# Audio.net
KiCad netlist of a schematic drawn in Altium Designer
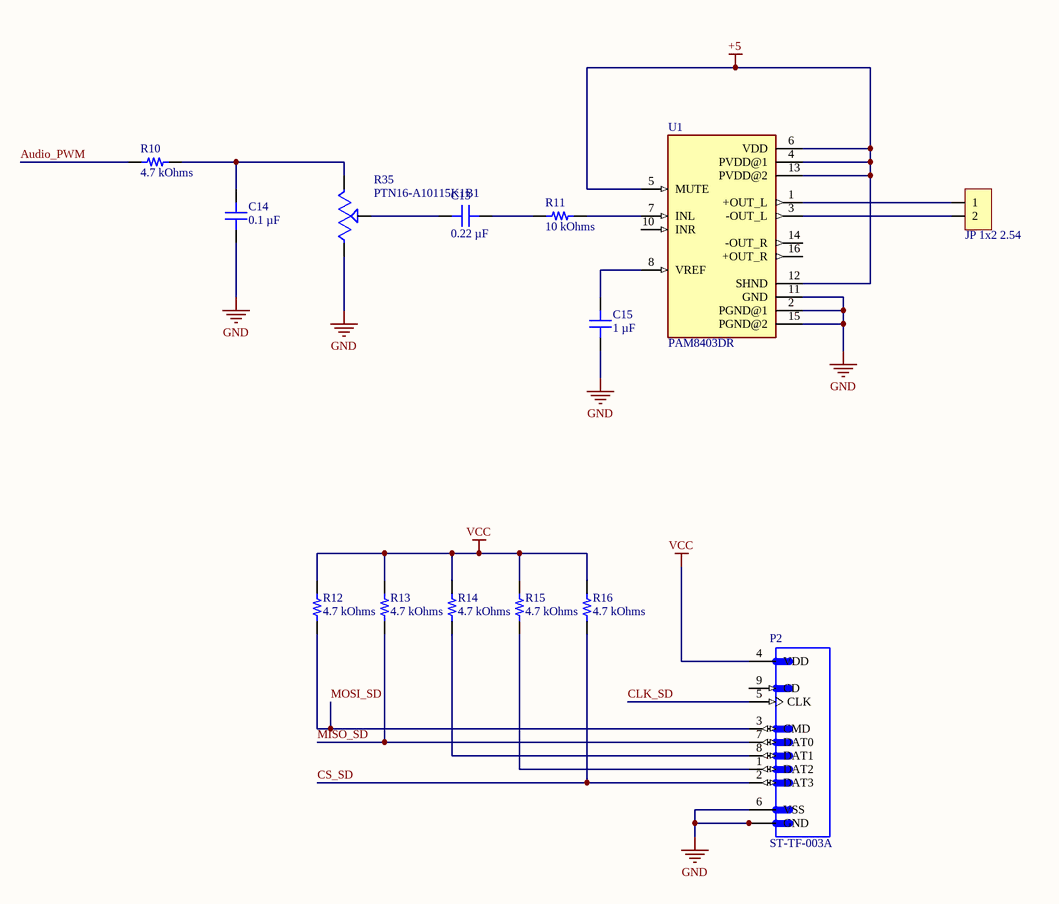
[diagram p0: Audio.SchDoc]

(export (version "E")
  (design (tool "Eeschema 10.0.6"))
  (components
    (comp (ref "C13")
      (value "0.22 µF")
      (footprint "CAP 0603_1608")
      (description "CAP CER 0.22UF 10V X7R 0603")
      (fields (field (name "PART NUMBER") "KGM15BR71A224MT") (field (name "MANUFACTURER") "KYOCERA AVX"))
      (libsource (lib "Celestial Altium Library - altium_library") (part "Capacitor"))
    )
    (comp (ref "C14")
      (value "0.1 µF")
      (footprint "CAP 0603_1608")
      (description "CAP CER 0.1UF 10V X7R 0603")
      (fields
        (field (name "PART NUMBER") "CX0603MRX7R6BB104")
        (field (name "MANUFACTURER") "PulseLarsen Antennas")
      )
      (libsource (lib "Celestial Altium Library - altium_library") (part "Capacitor"))
    )
    (comp (ref "C15")
      (value "1 µF")
      (footprint "CAP 0603_1608")
      (description "CAP CER 1UF 10V X7R 0603")
      (fields (field (name "PART NUMBER") "CM105X7R105M10AT") (field (name "MANUFACTURER") "KYOCERA AVX"))
      (libsource (lib "Celestial Altium Library - altium_library") (part "Capacitor"))
    )
    (comp (ref "JP5")
      (value "JP 1x2 2.54")
      (footprint "JP 1x2 CT")
      (description "Cắm")
      (libsource (lib "Jump") (part "JP 1x2 2.54 Cai Thang"))
    )
    (comp (ref "P2")
      (value "ST-TF-003A")
      (footprint "SUNTECH_ST-TF-003A")
      (description "Micro SD Card Socket")
      (libsource (lib "ST-TF-003A") (part "ST-TF-003A"))
    )
    (comp (ref "R10")
      (value "4.7 kOhms")
      (footprint "RES 0603_1608")
      (description "RES SMD 4.7K OHM 0.1% 1/10W 0603")
      (fields
        (field (name "PART NUMBER") "ERA-3ARB472V")
        (field (name "MANUFACTURER") "Panasonic Electronic Components")
      )
      (libsource (lib "Celestial Altium Library - altium_library") (part "Resistor"))
    )
    (comp (ref "R11")
      (value "10 kOhms")
      (footprint "RES 0603_1608")
      (description "RES SMD 10K OHM 0.1% 1/10W 0603")
      (fields
        (field (name "PART NUMBER") "MCT06030E1002BP100")
        (field (name "MANUFACTURER") "Vishay Beyschlag")
      )
      (libsource (lib "Celestial Altium Library - altium_library") (part "Resistor"))
    )
    (comp (ref "R12")
      (value "4.7 kOhms")
      (footprint "RES 0603_1608")
      (description "RES SMD 4.7KOHM 0.01% 1/16W 0603")
      (fields (field (name "PART NUMBER") "URG1608L-472-L-T05") (field (name "MANUFACTURER") "Susumu"))
      (libsource (lib "Celestial Altium Library - altium_library") (part "Resistor"))
    )
    (comp (ref "R13")
      (value "4.7 kOhms")
      (footprint "RES 0603_1608")
      (description "RES SMD 4.7KOHM 0.01% 1/16W 0603")
      (fields (field (name "PART NUMBER") "URG1608L-472-L-T05") (field (name "MANUFACTURER") "Susumu"))
      (libsource (lib "Celestial Altium Library - altium_library") (part "Resistor"))
    )
    (comp (ref "R14")
      (value "4.7 kOhms")
      (footprint "RES 0603_1608")
      (description "RES SMD 4.7KOHM 0.01% 1/16W 0603")
      (fields (field (name "PART NUMBER") "URG1608L-472-L-T05") (field (name "MANUFACTURER") "Susumu"))
      (libsource (lib "Celestial Altium Library - altium_library") (part "Resistor"))
    )
    (comp (ref "R15")
      (value "4.7 kOhms")
      (footprint "RES 0603_1608")
      (description "RES SMD 4.7KOHM 0.01% 1/16W 0603")
      (fields (field (name "PART NUMBER") "URG1608L-472-L-T05") (field (name "MANUFACTURER") "Susumu"))
      (libsource (lib "Celestial Altium Library - altium_library") (part "Resistor"))
    )
    (comp (ref "R16")
      (value "4.7 kOhms")
      (footprint "RES 0603_1608")
      (description "RES SMD 4.7KOHM 0.01% 1/16W 0603")
      (fields (field (name "PART NUMBER") "URG1608L-472-L-T05") (field (name "MANUFACTURER") "Susumu"))
      (libsource (lib "Celestial Altium Library - altium_library") (part "Resistor"))
    )
    (comp (ref "R35")
      (value "PTN16-A10115K1B1")
      (footprint "POT_PTN16-A10115K1B1")
      (fields (field (name "MF") "{'manufacturer': u'CUI Devices'}"))
      (libsource (lib "PTN16-A10115K1B1") (part "PTN16-A10115K1B1"))
    )
    (comp (ref "U1")
      (value "PAM8403DR")
      (footprint "SOIC127P605X150-16N")
      (description "Amplifier IC 2-Channel _Stereo_ Class D 16-SOP")
      (fields (field (name "MF") "Diodes Inc."))
      (libsource (lib "PAM8403DR") (part "PAM8403DR"))
    )
  )
  (nets
    (net (code "1") (name "+5") (class "Default")
      (node (ref "U1") (pin "12") (pinfunction "SHND_12") (pintype "power_in"))
      (node (ref "U1") (pin "13") (pinfunction "PVDD@2_13") (pintype "power_in"))
      (node (ref "U1") (pin "4") (pinfunction "PVDD@1_4") (pintype "power_in"))
      (node (ref "U1") (pin "5") (pinfunction "MUTE_5") (pintype "input"))
      (node (ref "U1") (pin "6") (pinfunction "VDD_6") (pintype "power_in"))
    )
    (net (code "2") (name "/Audio_PWM") (class "Default")
      (node (ref "R10") (pin "1") (pinfunction "1_1") (pintype "passive"))
    )
    (net (code "3") (name "/CLK_SD") (class "Default")
      (node (ref "P2") (pin "5") (pinfunction "CLK_5") (pintype "input"))
    )
    (net (code "4") (name "/CS_SD") (class "Default")
      (node (ref "P2") (pin "2") (pinfunction "DAT3_2") (pintype "bidirectional"))
      (node (ref "R16") (pin "1") (pinfunction "1_1") (pintype "passive"))
    )
    (net (code "5") (name "/MISO_SD") (class "Default")
      (node (ref "P2") (pin "7") (pinfunction "DAT0_7") (pintype "bidirectional"))
      (node (ref "R13") (pin "1") (pinfunction "1_1") (pintype "passive"))
    )
    (net (code "6") (name "/MOSI_SD") (class "Default")
      (node (ref "P2") (pin "3") (pinfunction "CMD_3") (pintype "bidirectional"))
      (node (ref "R12") (pin "1") (pinfunction "1_1") (pintype "passive"))
    )
    (net (code "7") (name "GND") (class "Default")
      (node (ref "C14") (pin "1") (pinfunction "1_1") (pintype "passive"))
      (node (ref "C15") (pin "1") (pinfunction "1_1") (pintype "passive"))
      (node (ref "P2") (pin "6") (pinfunction "VSS_6") (pintype "passive"))
      (node (ref "P2") (pin "G1") (pinfunction "GND_G1") (pintype "passive"))
      (node (ref "P2") (pin "G2") (pinfunction "GND_G2") (pintype "passive"))
      (node (ref "P2") (pin "G3") (pinfunction "GND_G3") (pintype "passive"))
      (node (ref "P2") (pin "G4") (pinfunction "GND_G4") (pintype "passive"))
      (node (ref "R35") (pin "1") (pinfunction "1_1") (pintype "passive"))
      (node (ref "U1") (pin "11") (pinfunction "GND_11") (pintype "power_in"))
      (node (ref "U1") (pin "15") (pinfunction "PGND@2_15") (pintype "power_in"))
      (node (ref "U1") (pin "2") (pinfunction "PGND@1_2") (pintype "power_in"))
    )
    (net (code "8") (name "Net-(C13-Pad1)") (class "Default")
      (node (ref "C13") (pin "1") (pinfunction "1_1") (pintype "passive"))
      (node (ref "R35") (pin "2") (pinfunction "2_2") (pintype "passive"))
    )
    (net (code "9") (name "Net-(C13-Pad2)") (class "Default")
      (node (ref "C13") (pin "2") (pinfunction "2_2") (pintype "passive"))
      (node (ref "R11") (pin "1") (pinfunction "1_1") (pintype "passive"))
    )
    (net (code "10") (name "Net-(C14-Pad2)") (class "Default")
      (node (ref "C14") (pin "2") (pinfunction "2_2") (pintype "passive"))
      (node (ref "R10") (pin "2") (pinfunction "2_2") (pintype "passive"))
      (node (ref "R35") (pin "3") (pinfunction "3_3") (pintype "passive"))
    )
    (net (code "11") (name "Net-(P2-DAT1)") (class "Default")
      (node (ref "P2") (pin "8") (pinfunction "DAT1_8") (pintype "bidirectional"))
      (node (ref "R14") (pin "1") (pinfunction "1_1") (pintype "passive"))
    )
    (net (code "12") (name "Net-(P2-DAT2)") (class "Default")
      (node (ref "P2") (pin "1") (pinfunction "DAT2_1") (pintype "bidirectional"))
      (node (ref "R15") (pin "1") (pinfunction "1_1") (pintype "passive"))
    )
    (net (code "13") (name "Net-(U1-+OUT_L)") (class "Default")
      (node (ref "JP5") (pin "1") (pinfunction "1_1") (pintype "passive"))
      (node (ref "U1") (pin "1") (pinfunction "+OUT_L_1") (pintype "output"))
    )
    (net (code "14") (name "Net-(U1--OUT_L)") (class "Default")
      (node (ref "JP5") (pin "2") (pinfunction "2_2") (pintype "passive"))
      (node (ref "U1") (pin "3") (pinfunction "-OUT_L_3") (pintype "output"))
    )
    (net (code "15") (name "Net-(U1-INL)") (class "Default")
      (node (ref "R11") (pin "2") (pinfunction "2_2") (pintype "passive"))
      (node (ref "U1") (pin "7") (pinfunction "INL_7") (pintype "input"))
    )
    (net (code "16") (name "Net-(U1-VREF)") (class "Default")
      (node (ref "C15") (pin "2") (pinfunction "2_2") (pintype "passive"))
      (node (ref "U1") (pin "8") (pinfunction "VREF_8") (pintype "input"))
    )
    (net (code "17") (name "VCC") (class "Default")
      (node (ref "P2") (pin "4") (pinfunction "VDD_4") (pintype "power_in"))
      (node (ref "R12") (pin "2") (pinfunction "2_2") (pintype "passive"))
      (node (ref "R13") (pin "2") (pinfunction "2_2") (pintype "passive"))
      (node (ref "R14") (pin "2") (pinfunction "2_2") (pintype "passive"))
      (node (ref "R15") (pin "2") (pinfunction "2_2") (pintype "passive"))
      (node (ref "R16") (pin "2") (pinfunction "2_2") (pintype "passive"))
    )
    (net (code "18") (name "unconnected-(P2-CD-Pad9)") (class "Default")
      (node (ref "P2") (pin "9") (pinfunction "CD_9") (pintype "input"))
    )
    (net (code "19") (name "unconnected-(U1-+OUT_R-Pad16)") (class "Default")
      (node (ref "U1") (pin "16") (pinfunction "+OUT_R_16") (pintype "output"))
    )
    (net (code "20") (name "unconnected-(U1--OUT_R-Pad14)") (class "Default")
      (node (ref "U1") (pin "14") (pinfunction "-OUT_R_14") (pintype "output"))
    )
    (net (code "21") (name "unconnected-(U1-INR-Pad10)") (class "Default")
      (node (ref "U1") (pin "10") (pinfunction "INR_10") (pintype "input"))
    )
  )
)
